# 07_RS485.net
KiCad netlist of a schematic drawn in Altium Designer
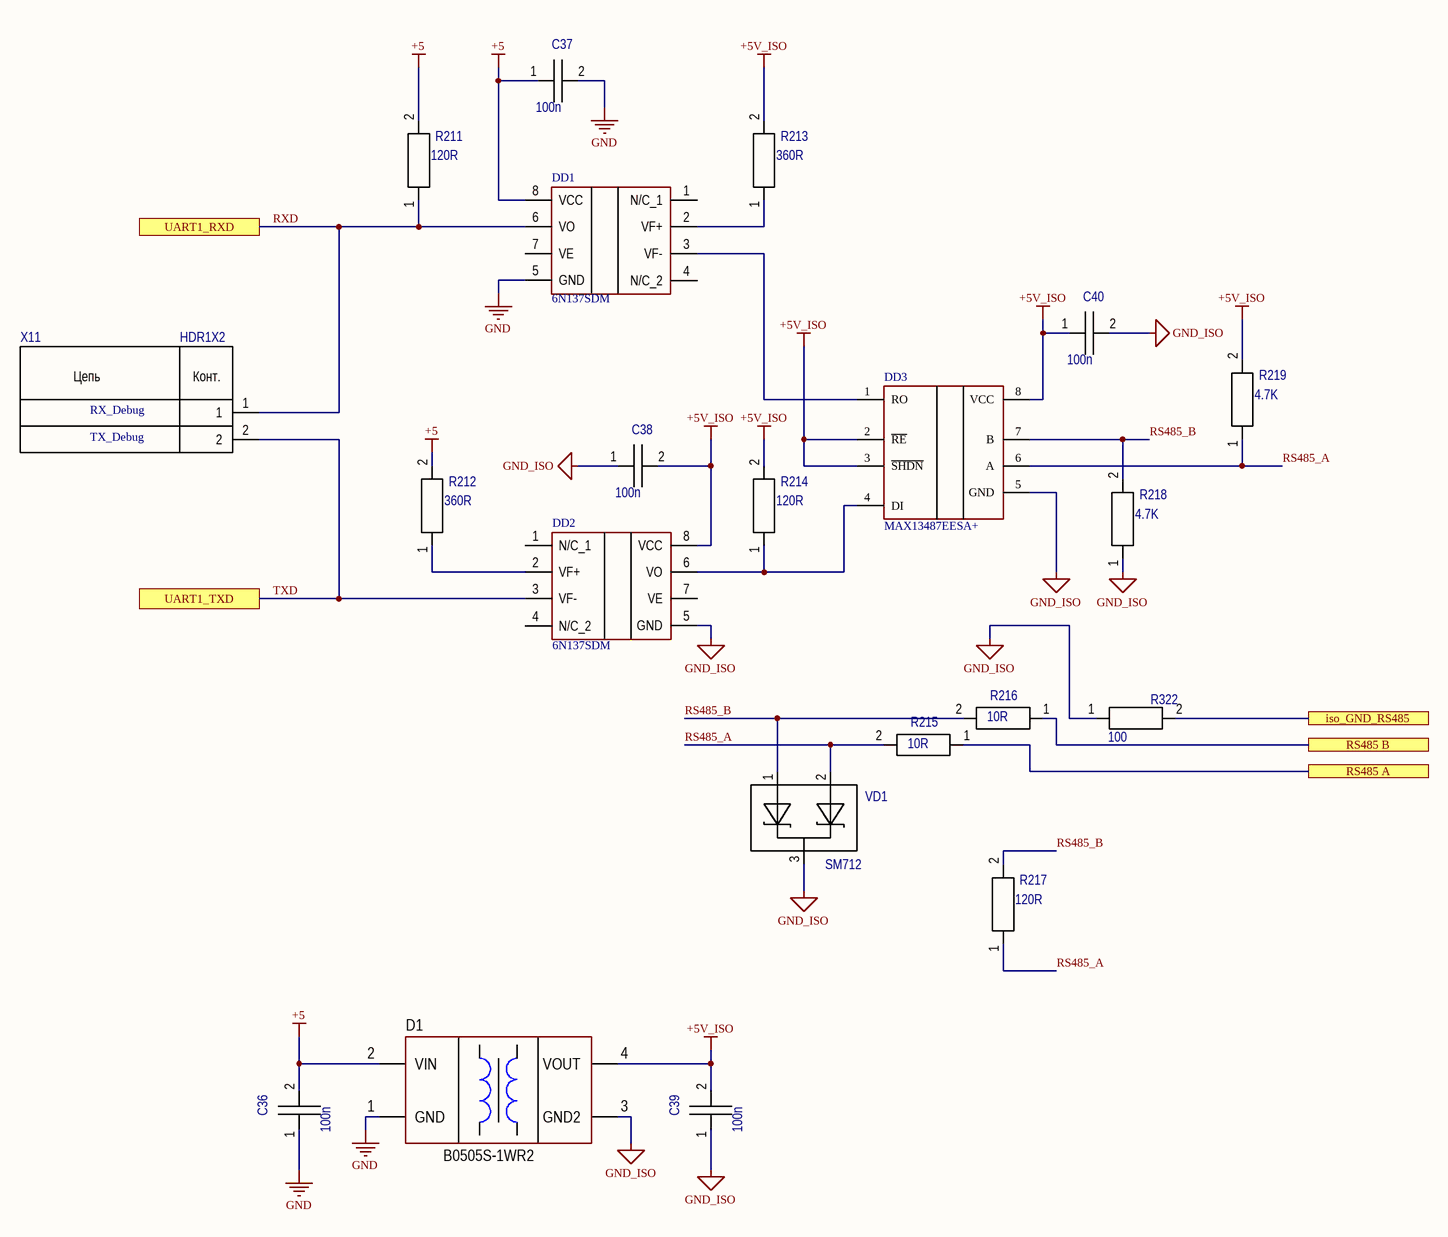
[diagram p0: 07_RS485.SchDoc]

(export (version "E")
  (design (tool "Eeschema 10.0.6"))
  (components
    (comp (ref "C36")
      (value "100n")
      (footprint "C0603")
      (fields
        (field (name "PART NUMBER") "GRM188R72A104KA35D")
        (field (name "TOLERANCE") "±10%")
        (field (name "MANUFACTURER") "Murata Manufacturing")
      )
      (libsource (lib "AccessLibrary") (part "Capacitor"))
    )
    (comp (ref "C37")
      (value "100n")
      (footprint "C0603")
      (fields
        (field (name "PART NUMBER") "GRM188R72A104KA35D")
        (field (name "TOLERANCE") "±10%")
        (field (name "MANUFACTURER") "Murata Manufacturing")
      )
      (libsource (lib "AccessLibrary") (part "Capacitor"))
    )
    (comp (ref "C38")
      (value "100n")
      (footprint "C0603")
      (fields
        (field (name "PART NUMBER") "GRM188R72A104KA35D")
        (field (name "TOLERANCE") "±10%")
        (field (name "MANUFACTURER") "Murata Manufacturing")
      )
      (libsource (lib "AccessLibrary") (part "Capacitor"))
    )
    (comp (ref "C39")
      (value "100n")
      (footprint "C0603")
      (fields
        (field (name "PART NUMBER") "GRM188R72A104KA35D")
        (field (name "TOLERANCE") "±10%")
        (field (name "MANUFACTURER") "Murata Manufacturing")
      )
      (libsource (lib "AccessLibrary") (part "Capacitor"))
    )
    (comp (ref "C40")
      (value "100n")
      (footprint "C0603")
      (fields
        (field (name "PART NUMBER") "GRM188R72A104KA35D")
        (field (name "TOLERANCE") "±10%")
        (field (name "MANUFACTURER") "Murata Manufacturing")
      )
      (libsource (lib "AccessLibrary") (part "Capacitor"))
    )
    (comp (ref "D1")
      (value "~")
      (footprint "MOD: SIP-4 (B0505S-1W)")
      (description "DC/DC converter")
      (fields
        (field (name "MANUFACTURER") "Mornsun")
        (field (name "VALUEMANUFACTURERPARTNUMBER") "DC/DC converter, isolator, 5V 200mA, -40...+105°C, SIP-4")
        (field (name "PARTNUMBER") "B0505S-1WR2")
      )
      (libsource (lib "board") (part "B0505S-1WR2"))
    )
    (comp (ref "DD1")
      (value "6N137SDM")
      (footprint "board:SOP254P1030X508-8N")
      (description "Integrated Circuit")
      (fields (field (name "MOUSER PART NUMBER") "512-6N137SDM"))
      (libsource (lib "") (part "6N137SDM_1"))
    )
    (comp (ref "DD2")
      (value "6N137SDM")
      (footprint "board:SOP254P1030X508-8N")
      (description "Integrated Circuit")
      (fields (field (name "MOUSER PART NUMBER") "512-6N137SDM"))
      (libsource (lib "board") (part "6N137SDM"))
    )
    (comp (ref "DD3")
      (value "MAX13487EESA+")
      (footprint "board:SOIC127P600X175-8N")
      (description "Integrated Circuit")
      (fields (field (name "MOUSER PART NUMBER") "700-MAX13487EESA"))
      (libsource (lib "board") (part "MAX13487EESA+"))
    )
    (comp (ref "R211")
      (value "120R")
      (footprint "RESC1608N")
      (fields
        (field (name "PART NUMBER") "RC0603FR-07120RL")
        (field (name "TOLERANCE") "±1%")
        (field (name "MANUFACTURER") "Тайвань")
      )
      (libsource (lib "AccessLibrary") (part "Resistor"))
    )
    (comp (ref "R212")
      (value "360R")
      (footprint "RESC1608N")
      (fields
        (field (name "PART NUMBER") "RC0603FR-07360RL")
        (field (name "TOLERANCE") "±1%")
        (field (name "MANUFACTURER") "Тайвань")
      )
      (libsource (lib "AccessLibrary") (part "Resistor"))
    )
    (comp (ref "R213")
      (value "360R")
      (footprint "RESC1608N")
      (fields
        (field (name "PART NUMBER") "RC0603FR-07360RL")
        (field (name "TOLERANCE") "±1%")
        (field (name "MANUFACTURER") "Тайвань")
      )
      (libsource (lib "AccessLibrary") (part "Resistor"))
    )
    (comp (ref "R214")
      (value "120R")
      (footprint "RESC1608N")
      (fields
        (field (name "PART NUMBER") "RC0603FR-07120RL")
        (field (name "TOLERANCE") "±1%")
        (field (name "MANUFACTURER") "Тайвань")
      )
      (libsource (lib "AccessLibrary") (part "Resistor"))
    )
    (comp (ref "R215")
      (value "10R")
      (footprint "RESC1608N")
      (fields
        (field (name "PART NUMBER") "RC0603FR-0710RL")
        (field (name "TOLERANCE") "±1%")
        (field (name "MANUFACTURER") "Тайвань")
      )
      (libsource (lib "AccessLibrary") (part "Resistor"))
    )
    (comp (ref "R216")
      (value "10R")
      (footprint "RESC1608N")
      (fields
        (field (name "PART NUMBER") "RC0603FR-0710RL")
        (field (name "TOLERANCE") "±1%")
        (field (name "MANUFACTURER") "Тайвань")
      )
      (libsource (lib "AccessLibrary") (part "Resistor"))
    )
    (comp (ref "R217")
      (value "120R")
      (footprint "RESC1608N")
      (fields
        (field (name "PART NUMBER") "RC0603FR-07120RL")
        (field (name "TOLERANCE") "±1%")
        (field (name "MANUFACTURER") "Тайвань")
      )
      (libsource (lib "AccessLibrary") (part "Resistor"))
    )
    (comp (ref "R218")
      (value "4.7K")
      (footprint "RESC1608N")
      (fields
        (field (name "PART NUMBER") "RC0603FR-074K7L")
        (field (name "TOLERANCE") "±1%")
        (field (name "MANUFACTURER") "Тайвань")
      )
      (libsource (lib "AccessLibrary") (part "Resistor"))
    )
    (comp (ref "R219")
      (value "4.7K")
      (footprint "RESC1608N")
      (fields
        (field (name "PART NUMBER") "RC0603FR-074K7L")
        (field (name "TOLERANCE") "±1%")
        (field (name "MANUFACTURER") "Тайвань")
      )
      (libsource (lib "AccessLibrary") (part "Resistor"))
    )
    (comp (ref "R322")
      (value "100")
      (footprint "RESC3216N")
      (fields
        (field (name "PART NUMBER") "RC1206FR-07100RL")
        (field (name "TOLERANCE") "±1%")
        (field (name "Comment") "R1206")
      )
      (libsource (lib "AccessLibrary") (part "Resistor"))
    )
    (comp (ref "VD1")
      (value "SM712")
      (footprint "SOT23-3N")
      (fields
        (field (name "COM") "SM712")
        (field (name "PART NUMBER") "SM712.TCT")
        (field (name "MANUFACTURER") "Semtech")
      )
      (libsource (lib "AccessLibrary") (part "DiodeShottky_BAT54C"))
    )
    (comp (ref "X11")
      (value "HDR1X2")
      (footprint "HDR1X2")
      (fields (field (name "MANUFACTURER") "Dinkle Enterprise"))
      (libsource (lib "AccessLibrary") (part "HDR1X2"))
    )
  )
  (nets
    (net (code "1") (name "+5") (class "Default")
      (node (ref "C36") (pin "2") (pinfunction "2_2") (pintype "passive"))
      (node (ref "C37") (pin "1") (pinfunction "1_1") (pintype "passive"))
      (node (ref "D1") (pin "2") (pinfunction "VIN_2") (pintype "power_in"))
      (node (ref "DD1") (pin "8") (pinfunction "VCC_8") (pintype "passive"))
      (node (ref "R211") (pin "2") (pinfunction "2_2") (pintype "passive"))
      (node (ref "R212") (pin "2") (pinfunction "2_2") (pintype "passive"))
    )
    (net (code "2") (name "+5V_ISO") (class "Default")
      (node (ref "C38") (pin "2") (pinfunction "2_2") (pintype "passive"))
      (node (ref "C39") (pin "2") (pinfunction "2_2") (pintype "passive"))
      (node (ref "C40") (pin "1") (pinfunction "1_1") (pintype "passive"))
      (node (ref "D1") (pin "4") (pinfunction "VOUT_4") (pintype "power_in"))
      (node (ref "DD2") (pin "8") (pinfunction "VCC_8") (pintype "passive"))
      (node (ref "DD3") (pin "2") (pinfunction "~{RE}_2") (pintype "passive"))
      (node (ref "DD3") (pin "3") (pinfunction "~{SHDN}_3") (pintype "passive"))
      (node (ref "DD3") (pin "8") (pinfunction "VCC_8") (pintype "passive"))
      (node (ref "R213") (pin "2") (pinfunction "2_2") (pintype "passive"))
      (node (ref "R214") (pin "2") (pinfunction "2_2") (pintype "passive"))
      (node (ref "R219") (pin "2") (pinfunction "2_2") (pintype "passive"))
    )
    (net (code "3") (name "/RS485 A") (class "Default")
      (node (ref "R215") (pin "1") (pinfunction "1_1") (pintype "passive"))
    )
    (net (code "4") (name "/RS485 B") (class "Default")
      (node (ref "R216") (pin "1") (pinfunction "1_1") (pintype "passive"))
    )
    (net (code "5") (name "/RS485_A") (class "Default")
      (node (ref "DD3") (pin "6") (pinfunction "A_6") (pintype "passive"))
      (node (ref "R215") (pin "2") (pinfunction "2_2") (pintype "passive"))
      (node (ref "R217") (pin "1") (pinfunction "1_1") (pintype "passive"))
      (node (ref "R219") (pin "1") (pinfunction "1_1") (pintype "passive"))
      (node (ref "VD1") (pin "2") (pinfunction "2_2") (pintype "passive"))
    )
    (net (code "6") (name "/RS485_B") (class "Default")
      (node (ref "DD3") (pin "7") (pinfunction "B_7") (pintype "passive"))
      (node (ref "R216") (pin "2") (pinfunction "2_2") (pintype "passive"))
      (node (ref "R217") (pin "2") (pinfunction "2_2") (pintype "passive"))
      (node (ref "R218") (pin "2") (pinfunction "2_2") (pintype "passive"))
      (node (ref "VD1") (pin "1") (pinfunction "1_1") (pintype "passive"))
    )
    (net (code "7") (name "/RXD") (class "Default")
      (node (ref "DD1") (pin "6") (pinfunction "VO_6") (pintype "passive"))
      (node (ref "R211") (pin "1") (pinfunction "1_1") (pintype "passive"))
      (node (ref "X11") (pin "1") (pinfunction "1_1") (pintype "passive"))
    )
    (net (code "8") (name "/TXD") (class "Default")
      (node (ref "DD2") (pin "3") (pinfunction "VF-_3") (pintype "passive"))
      (node (ref "X11") (pin "2") (pinfunction "2_2") (pintype "passive"))
    )
    (net (code "9") (name "/iso_GND_RS485") (class "Default")
      (node (ref "R322") (pin "2") (pinfunction "2_2") (pintype "passive"))
    )
    (net (code "10") (name "GND") (class "Default")
      (node (ref "C36") (pin "1") (pinfunction "1_1") (pintype "passive"))
      (node (ref "C37") (pin "2") (pinfunction "2_2") (pintype "passive"))
      (node (ref "D1") (pin "1") (pinfunction "GND_1") (pintype "power_in"))
      (node (ref "DD1") (pin "5") (pinfunction "GND_5") (pintype "passive"))
    )
    (net (code "11") (name "GND_ISO") (class "Default")
      (node (ref "C38") (pin "1") (pinfunction "1_1") (pintype "passive"))
      (node (ref "C39") (pin "1") (pinfunction "1_1") (pintype "passive"))
      (node (ref "C40") (pin "2") (pinfunction "2_2") (pintype "passive"))
      (node (ref "D1") (pin "3") (pinfunction "GND2_3") (pintype "power_in"))
      (node (ref "DD2") (pin "5") (pinfunction "GND_5") (pintype "passive"))
      (node (ref "DD3") (pin "5") (pinfunction "GND_5") (pintype "passive"))
      (node (ref "R218") (pin "1") (pinfunction "1_1") (pintype "passive"))
      (node (ref "R322") (pin "1") (pinfunction "1_1") (pintype "passive"))
      (node (ref "VD1") (pin "3") (pinfunction "3_3") (pintype "passive"))
    )
    (net (code "12") (name "Net-(DD1-VF+)") (class "Default")
      (node (ref "DD1") (pin "2") (pinfunction "VF+_2") (pintype "passive"))
      (node (ref "R213") (pin "1") (pinfunction "1_1") (pintype "passive"))
    )
    (net (code "13") (name "Net-(DD1-VF-)") (class "Default")
      (node (ref "DD1") (pin "3") (pinfunction "VF-_3") (pintype "passive"))
      (node (ref "DD3") (pin "1") (pinfunction "RO_1") (pintype "passive"))
    )
    (net (code "14") (name "Net-(DD2-VF+)") (class "Default")
      (node (ref "DD2") (pin "2") (pinfunction "VF+_2") (pintype "passive"))
      (node (ref "R212") (pin "1") (pinfunction "1_1") (pintype "passive"))
    )
    (net (code "15") (name "Net-(DD2-VO)") (class "Default")
      (node (ref "DD2") (pin "6") (pinfunction "VO_6") (pintype "passive"))
      (node (ref "DD3") (pin "4") (pinfunction "DI_4") (pintype "passive"))
      (node (ref "R214") (pin "1") (pinfunction "1_1") (pintype "passive"))
    )
    (net (code "16") (name "unconnected-(DD1-N{slash}C_1-Pad1)") (class "Default")
      (node (ref "DD1") (pin "1") (pinfunction "N/C_1_1") (pintype "passive"))
    )
    (net (code "17") (name "unconnected-(DD1-N{slash}C_2-Pad4)") (class "Default")
      (node (ref "DD1") (pin "4") (pinfunction "N/C_2_4") (pintype "passive"))
    )
    (net (code "18") (name "unconnected-(DD1-VE-Pad7)") (class "Default")
      (node (ref "DD1") (pin "7") (pinfunction "VE_7") (pintype "passive"))
    )
    (net (code "19") (name "unconnected-(DD2-N{slash}C_1-Pad1)") (class "Default")
      (node (ref "DD2") (pin "1") (pinfunction "N/C_1_1") (pintype "passive"))
    )
    (net (code "20") (name "unconnected-(DD2-N{slash}C_2-Pad4)") (class "Default")
      (node (ref "DD2") (pin "4") (pinfunction "N/C_2_4") (pintype "passive"))
    )
    (net (code "21") (name "unconnected-(DD2-VE-Pad7)") (class "Default")
      (node (ref "DD2") (pin "7") (pinfunction "VE_7") (pintype "passive"))
    )
  )
)
